# DS2482-LC24XX-breakout.net
KiCad netlist of a schematic drawn in EAGLE
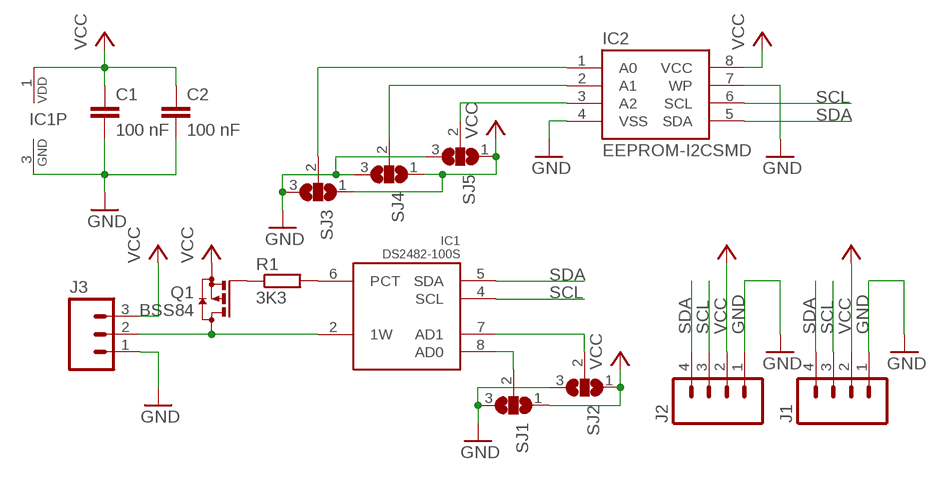
[diagram p0: schematic, sheet 1]

(export (version "E")
  (design (tool "Eeschema 10.0.6"))
  (components
    (comp (ref "C1")
      (value "100 nF")
      (footprint "eagle-import:C0603")
      (libsource (lib "eagle-import") (part "C-EUC0603"))
    )
    (comp (ref "C2")
      (value "100 nF")
      (footprint "eagle-import:C0603")
      (libsource (lib "eagle-import") (part "C-EUC0603"))
    )
    (comp (ref "IC1")
      (value "DS2482-100S")
      (footprint "eagle-import:SO08")
      (libsource (lib "eagle-import") (part "DS2482-100S"))
    )
    (comp (ref "IC2")
      (value "EEPROM-I2CSMD")
      (footprint "eagle-import:SO08")
      (libsource (lib "eagle-import") (part "EEPROM-I2CSMD"))
    )
    (comp (ref "J1")
      (value "M04PTH")
      (footprint "eagle-import:1X04")
      (libsource (lib "eagle-import") (part "M04PTH"))
    )
    (comp (ref "J2")
      (value "M04PTH")
      (footprint "eagle-import:1X04")
      (libsource (lib "eagle-import") (part "M04PTH"))
    )
    (comp (ref "J3")
      (value "M03PTH")
      (footprint "eagle-import:1X03")
      (libsource (lib "eagle-import") (part "M03PTH"))
    )
    (comp (ref "Q1")
      (value "BSS84")
      (footprint "eagle-import:SOT23")
      (libsource (lib "eagle-import") (part "BSS84"))
    )
    (comp (ref "R1")
      (value "3K3")
      (footprint "eagle-import:R0805")
      (libsource (lib "eagle-import") (part "R-EU_R0805"))
    )
    (comp (ref "SJ1")
      (value "SJ2W")
      (footprint "eagle-import:SJ_2")
      (libsource (lib "eagle-import") (part "SJ2W"))
    )
    (comp (ref "SJ2")
      (value "SJ2W")
      (footprint "eagle-import:SJ_2")
      (libsource (lib "eagle-import") (part "SJ2W"))
    )
    (comp (ref "SJ3")
      (value "SJ2W")
      (footprint "eagle-import:SJ_2")
      (libsource (lib "eagle-import") (part "SJ2W"))
    )
    (comp (ref "SJ4")
      (value "SJ2W")
      (footprint "eagle-import:SJ_2")
      (libsource (lib "eagle-import") (part "SJ2W"))
    )
    (comp (ref "SJ5")
      (value "SJ2W")
      (footprint "eagle-import:SJ_2")
      (libsource (lib "eagle-import") (part "SJ2W"))
    )
  )
  (nets
    (net (code "1") (name "/SCL") (class "Default")
      (node (ref "IC1") (pin "4") (pinfunction "SCL_4") (pintype "input"))
      (node (ref "IC2") (pin "6") (pinfunction "SCL_6") (pintype "bidirectional"))
      (node (ref "J1") (pin "3") (pinfunction "3_3") (pintype "passive"))
      (node (ref "J2") (pin "3") (pinfunction "3_3") (pintype "passive"))
    )
    (net (code "2") (name "/SDA") (class "Default")
      (node (ref "IC1") (pin "5") (pinfunction "SDA_5") (pintype "bidirectional"))
      (node (ref "IC2") (pin "5") (pinfunction "SDA_5") (pintype "bidirectional"))
      (node (ref "J1") (pin "4") (pinfunction "4_4") (pintype "passive"))
      (node (ref "J2") (pin "4") (pinfunction "4_4") (pintype "passive"))
    )
    (net (code "3") (name "GND") (class "Default")
      (node (ref "C1") (pin "2") (pinfunction "2_2") (pintype "passive"))
      (node (ref "C2") (pin "2") (pinfunction "2_2") (pintype "passive"))
      (node (ref "IC1") (pin "3") (pinfunction "GND_3") (pintype "power_in"))
      (node (ref "IC2") (pin "4") (pinfunction "VSS_4") (pintype "power_in"))
      (node (ref "IC2") (pin "7") (pinfunction "WP_7") (pintype "bidirectional"))
      (node (ref "J1") (pin "1") (pinfunction "1_1") (pintype "passive"))
      (node (ref "J2") (pin "1") (pinfunction "1_1") (pintype "passive"))
      (node (ref "J3") (pin "1") (pinfunction "1_1") (pintype "passive"))
      (node (ref "SJ1") (pin "3") (pinfunction "3_3") (pintype "passive"))
      (node (ref "SJ2") (pin "3") (pinfunction "3_3") (pintype "passive"))
      (node (ref "SJ3") (pin "3") (pinfunction "3_3") (pintype "passive"))
      (node (ref "SJ4") (pin "3") (pinfunction "3_3") (pintype "passive"))
      (node (ref "SJ5") (pin "3") (pinfunction "3_3") (pintype "passive"))
    )
    (net (code "4") (name "Net-(IC1A-1W)") (class "Default")
      (node (ref "IC1") (pin "2") (pinfunction "1W_2") (pintype "open_collector"))
      (node (ref "J3") (pin "2") (pinfunction "2_2") (pintype "passive"))
      (node (ref "Q1") (pin "3") (pinfunction "D_3") (pintype "passive"))
    )
    (net (code "5") (name "Net-(IC1A-AD0)") (class "Default")
      (node (ref "IC1") (pin "8") (pinfunction "AD0_8") (pintype "input"))
      (node (ref "SJ1") (pin "2") (pinfunction "2_2") (pintype "passive"))
    )
    (net (code "6") (name "Net-(IC1A-AD1)") (class "Default")
      (node (ref "IC1") (pin "7") (pinfunction "AD1_7") (pintype "input"))
      (node (ref "SJ2") (pin "2") (pinfunction "2_2") (pintype "passive"))
    )
    (net (code "7") (name "Net-(IC1A-PCT)") (class "Default")
      (node (ref "IC1") (pin "6") (pinfunction "PCT_6") (pintype "output"))
      (node (ref "R1") (pin "2") (pinfunction "2_2") (pintype "passive"))
    )
    (net (code "8") (name "Net-(IC2-A0)") (class "Default")
      (node (ref "IC2") (pin "1") (pinfunction "A0_1") (pintype "bidirectional"))
      (node (ref "SJ3") (pin "2") (pinfunction "2_2") (pintype "passive"))
    )
    (net (code "9") (name "Net-(IC2-A1)") (class "Default")
      (node (ref "IC2") (pin "2") (pinfunction "A1_2") (pintype "bidirectional"))
      (node (ref "SJ4") (pin "2") (pinfunction "2_2") (pintype "passive"))
    )
    (net (code "10") (name "Net-(IC2-A2)") (class "Default")
      (node (ref "IC2") (pin "3") (pinfunction "A2_3") (pintype "bidirectional"))
      (node (ref "SJ5") (pin "2") (pinfunction "2_2") (pintype "passive"))
    )
    (net (code "11") (name "Net-(Q1-G)") (class "Default")
      (node (ref "Q1") (pin "1") (pinfunction "G_1") (pintype "passive"))
      (node (ref "R1") (pin "1") (pinfunction "1_1") (pintype "passive"))
    )
    (net (code "12") (name "VCC") (class "Default")
      (node (ref "C1") (pin "1") (pinfunction "1_1") (pintype "passive"))
      (node (ref "C2") (pin "1") (pinfunction "1_1") (pintype "passive"))
      (node (ref "IC1") (pin "1") (pinfunction "VDD_1") (pintype "power_in"))
      (node (ref "IC2") (pin "8") (pinfunction "VCC_8") (pintype "power_in"))
      (node (ref "J1") (pin "2") (pinfunction "2_2") (pintype "passive"))
      (node (ref "J2") (pin "2") (pinfunction "2_2") (pintype "passive"))
      (node (ref "J3") (pin "3") (pinfunction "3_3") (pintype "passive"))
      (node (ref "Q1") (pin "2") (pinfunction "S_2") (pintype "passive"))
      (node (ref "SJ1") (pin "1") (pinfunction "1_1") (pintype "passive"))
      (node (ref "SJ2") (pin "1") (pinfunction "1_1") (pintype "passive"))
      (node (ref "SJ3") (pin "1") (pinfunction "1_1") (pintype "passive"))
      (node (ref "SJ4") (pin "1") (pinfunction "1_1") (pintype "passive"))
      (node (ref "SJ5") (pin "1") (pinfunction "1_1") (pintype "passive"))
    )
  )
)
